# BiDirCurrentSensor.net
KiCad netlist of a schematic drawn in Altium Designer
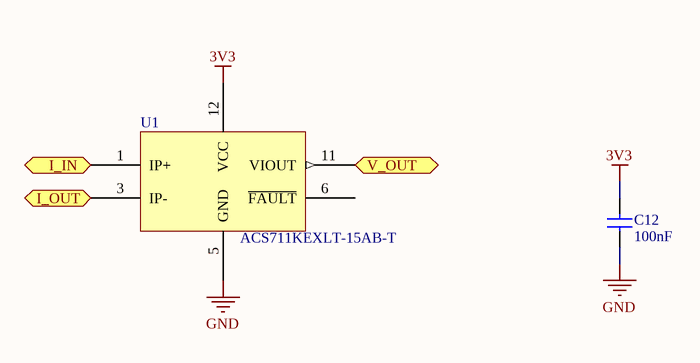
[diagram p0: BiDirCurrentSensor.SchDoc]

(export (version "E")
  (design (tool "Eeschema 10.0.6"))
  (components
    (comp (ref "C12")
      (value "100nF")
      (footprint "CAPC0603")
      (fields (field (name "Comment") "Cap"))
      (libsource (lib "Passives") (part "Cap"))
    )
    (comp (ref "U1")
      (value "ACS711KEXLT-15AB-T")
      (footprint "ACS711KEXLT")
      (libsource (lib "ICs") (part "ACS711EEXLT"))
    )
  )
  (nets
    (net (code "1") (name "/I_IN") (class "Default")
      (node (ref "U1") (pin "1") (pinfunction "IP+_1") (pintype "passive"))
    )
    (net (code "2") (name "/I_OUT") (class "Default")
      (node (ref "U1") (pin "3") (pinfunction "IP-_3") (pintype "passive"))
    )
    (net (code "3") (name "/V_OUT") (class "Default")
      (node (ref "U1") (pin "11") (pinfunction "VIOUT_11") (pintype "output"))
    )
    (net (code "4") (name "3V3") (class "Default")
      (node (ref "C12") (pin "2") (pinfunction "B_2") (pintype "passive"))
      (node (ref "U1") (pin "12") (pinfunction "VCC_12") (pintype "power_in"))
    )
    (net (code "5") (name "GND") (class "Default")
      (node (ref "C12") (pin "1") (pinfunction "A_1") (pintype "passive"))
      (node (ref "U1") (pin "5") (pinfunction "GND_5") (pintype "passive"))
    )
    (net (code "6") (name "unconnected-(U1-~{FAULT}-Pad6)") (class "Default")
      (node (ref "U1") (pin "6") (pinfunction "~{FAULT}_6") (pintype "open_collector"))
    )
  )
)
